# FPGA_MGT.net
KiCad netlist of a schematic drawn in Altium Designer
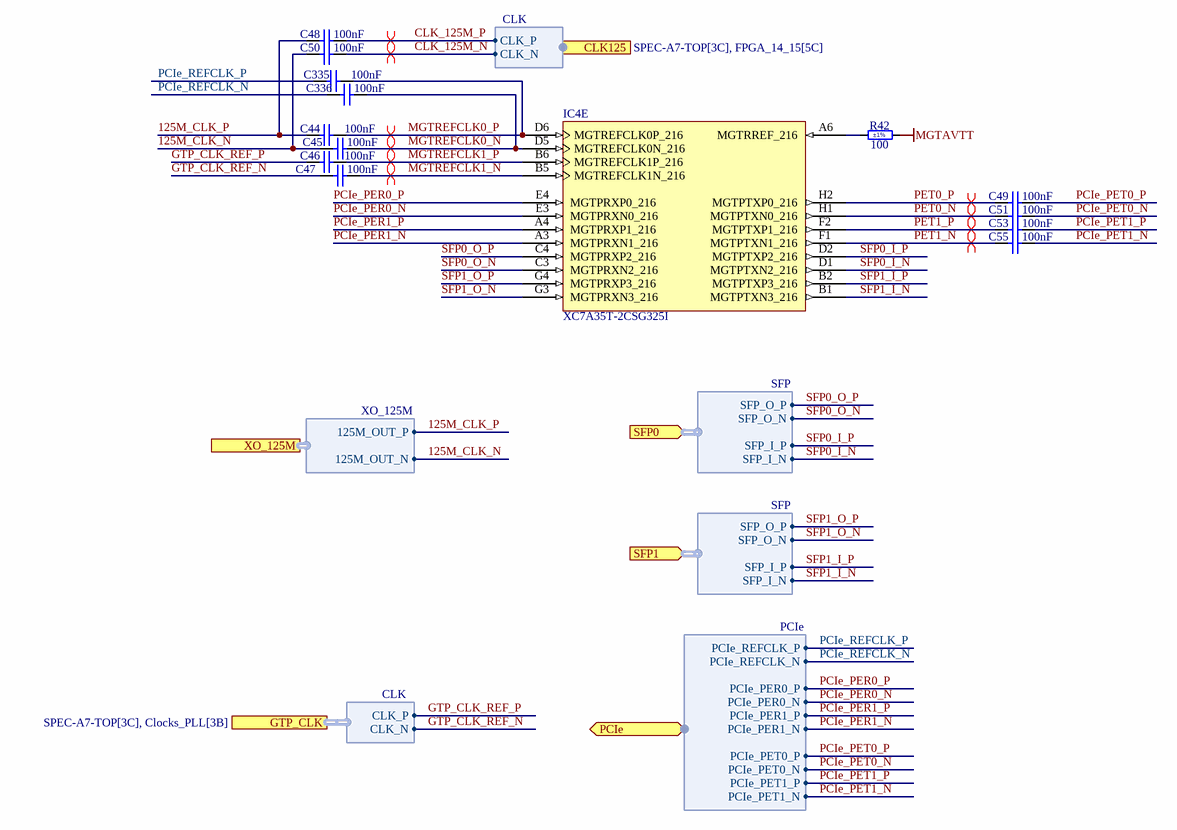
[diagram p0: FPGA_MGT.SchDoc]

(export (version "E")
  (design (tool "Eeschema 10.0.6"))
  (components
    (comp (ref "C44")
      (value "100nF")
      (footprint "CAPC0603X33N")
      (description "Non-polarised capacitor")
      (fields
        (field (name "PART NUMBER") "CC0201_100NF_6.3V_10%_X5R")
        (field (name "VOLTAGE") "6.3V")
        (field (name "AUTHOR") "CERN DEM JLC")
      )
      (libsource (lib "Capacitors") (part "Capacitor - non polarized"))
    )
    (comp (ref "C45")
      (value "100nF")
      (footprint "CAPC0603X33N")
      (description "Non-polarised capacitor")
      (fields
        (field (name "PART NUMBER") "CC0201_100NF_6.3V_10%_X5R")
        (field (name "VOLTAGE") "6.3V")
        (field (name "AUTHOR") "CERN DEM JLC")
      )
      (libsource (lib "Capacitors") (part "Capacitor - non polarized"))
    )
    (comp (ref "C46")
      (value "100nF")
      (footprint "CAPC0603X33N")
      (description "Non-polarised capacitor")
      (fields
        (field (name "PART NUMBER") "CC0201_100NF_6.3V_10%_X5R")
        (field (name "VOLTAGE") "6.3V")
        (field (name "AUTHOR") "CERN DEM JLC")
      )
      (libsource (lib "Capacitors") (part "Capacitor - non polarized"))
    )
    (comp (ref "C47")
      (value "100nF")
      (footprint "CAPC0603X33N")
      (description "Non-polarised capacitor")
      (fields
        (field (name "PART NUMBER") "CC0201_100NF_6.3V_10%_X5R")
        (field (name "VOLTAGE") "6.3V")
        (field (name "AUTHOR") "CERN DEM JLC")
      )
      (libsource (lib "Capacitors") (part "Capacitor - non polarized"))
    )
    (comp (ref "C48")
      (value "100nF")
      (footprint "CAPC0603X33N")
      (description "Non-polarised capacitor")
      (fields
        (field (name "PART NUMBER") "CC0201_100NF_6.3V_10%_X5R")
        (field (name "VOLTAGE") "6.3V")
        (field (name "AUTHOR") "CERN DEM JLC")
      )
      (libsource (lib "Capacitors") (part "Capacitor - non polarized"))
    )
    (comp (ref "C49")
      (value "100nF")
      (footprint "CAPC0603X33N")
      (description "Non-polarised capacitor")
      (fields
        (field (name "PART NUMBER") "CC0201_100NF_6.3V_10%_X5R")
        (field (name "VOLTAGE") "6.3V")
        (field (name "AUTHOR") "CERN DEM JLC")
      )
      (libsource (lib "Capacitors") (part "Capacitor - non polarized"))
    )
    (comp (ref "C50")
      (value "100nF")
      (footprint "CAPC0603X33N")
      (description "Non-polarised capacitor")
      (fields
        (field (name "PART NUMBER") "CC0201_100NF_6.3V_10%_X5R")
        (field (name "VOLTAGE") "6.3V")
        (field (name "AUTHOR") "CERN DEM JLC")
      )
      (libsource (lib "Capacitors") (part "Capacitor - non polarized"))
    )
    (comp (ref "C51")
      (value "100nF")
      (footprint "CAPC0603X33N")
      (description "Non-polarised capacitor")
      (fields
        (field (name "PART NUMBER") "CC0201_100NF_6.3V_10%_X5R")
        (field (name "VOLTAGE") "6.3V")
        (field (name "AUTHOR") "CERN DEM JLC")
      )
      (libsource (lib "Capacitors") (part "Capacitor - non polarized"))
    )
    (comp (ref "C53")
      (value "100nF")
      (footprint "CAPC0603X33N")
      (description "Non-polarised capacitor")
      (fields
        (field (name "PART NUMBER") "CC0201_100NF_6.3V_10%_X5R")
        (field (name "VOLTAGE") "6.3V")
        (field (name "AUTHOR") "CERN DEM JLC")
      )
      (libsource (lib "Capacitors") (part "Capacitor - non polarized"))
    )
    (comp (ref "C55")
      (value "100nF")
      (footprint "CAPC0603X33N")
      (description "Non-polarised capacitor")
      (fields
        (field (name "PART NUMBER") "CC0201_100NF_6.3V_10%_X5R")
        (field (name "VOLTAGE") "6.3V")
        (field (name "AUTHOR") "CERN DEM JLC")
      )
      (libsource (lib "Capacitors") (part "Capacitor - non polarized"))
    )
    (comp (ref "C335")
      (value "100nF")
      (footprint "CAPC0603X33N")
      (description "Non-polarised capacitor")
      (fields
        (field (name "PART NUMBER") "CC0201_100NF_6.3V_10%_X5R")
        (field (name "VOLTAGE") "6.3V")
        (field (name "AUTHOR") "CERN DEM JLC")
      )
      (libsource (lib "Capacitors") (part "Capacitor - non polarized"))
    )
    (comp (ref "C336")
      (value "100nF")
      (footprint "CAPC0603X33N")
      (description "Non-polarised capacitor")
      (fields
        (field (name "PART NUMBER") "CC0201_100NF_6.3V_10%_X5R")
        (field (name "VOLTAGE") "6.3V")
        (field (name "AUTHOR") "CERN DEM JLC")
      )
      (libsource (lib "Capacitors") (part "Capacitor - non polarized"))
    )
    (comp (ref "IC4")
      (value "XC7A35T-2CSG325I")
      (footprint "CSG325")
      (description "Artix-7 FPGA, 150 User I/Os, 4 GTP, 324-Ball BGA, Speed Grade 2, Industrial Grade, Pb-Free")
      (fields (field (name "MANUFACTURER") "Xilinx"))
      (libsource (lib "Altium Content Vault") (part "XLNX-XC7A35T-CSG325"))
    )
    (comp (ref "R42")
      (value "100")
      (footprint "RESC1005X40N")
      (description "Resistor - 1%")
      (fields
        (field (name "TOLERANCE") "±1%")
        (field (name "PART NUMBER") "R0402_100R_1%_0.0625W_100PPM")
        (field (name "POWER") "0.0625W")
        (field (name "AUTHOR") "CERN DEM JLC")
      )
      (libsource (lib "Resistors") (part "Resistor - 1%"))
    )
  )
  (nets
    (net (code "5") (name "/125M_CLK_N") (class "Default")
      (node (ref "C45") (pin "1") (pinfunction "1_1") (pintype "passive"))
      (node (ref "C50") (pin "1") (pinfunction "1_1") (pintype "passive"))
    )
    (net (code "6") (name "/125M_CLK_P") (class "Default")
      (node (ref "C44") (pin "1") (pinfunction "1_1") (pintype "passive"))
      (node (ref "C48") (pin "1") (pinfunction "1_1") (pintype "passive"))
    )
    (net (code "7") (name "/CLK_125M_N") (class "Default")
      (node (ref "C50") (pin "2") (pinfunction "2_2") (pintype "passive"))
    )
    (net (code "8") (name "/CLK_125M_P") (class "Default")
      (node (ref "C48") (pin "2") (pinfunction "2_2") (pintype "passive"))
    )
    (net (code "9") (name "/GTP_CLK_REF_N") (class "Default")
      (node (ref "C47") (pin "1") (pinfunction "1_1") (pintype "passive"))
    )
    (net (code "10") (name "/GTP_CLK_REF_P") (class "Default")
      (node (ref "C46") (pin "1") (pinfunction "1_1") (pintype "passive"))
    )
    (net (code "11") (name "/MGTREFCLK0_N") (class "Default")
      (node (ref "C336") (pin "2") (pinfunction "2_2") (pintype "passive"))
      (node (ref "C45") (pin "2") (pinfunction "2_2") (pintype "passive"))
      (node (ref "IC4") (pin "D5") (pinfunction "MGTREFCLK0N_216_D5") (pintype "input"))
    )
    (net (code "12") (name "/MGTREFCLK0_P") (class "Default")
      (node (ref "C335") (pin "2") (pinfunction "2_2") (pintype "passive"))
      (node (ref "C44") (pin "2") (pinfunction "2_2") (pintype "passive"))
      (node (ref "IC4") (pin "D6") (pinfunction "MGTREFCLK0P_216_D6") (pintype "input"))
    )
    (net (code "13") (name "/MGTREFCLK1_N") (class "Default")
      (node (ref "C47") (pin "2") (pinfunction "2_2") (pintype "passive"))
      (node (ref "IC4") (pin "B5") (pinfunction "MGTREFCLK1N_216_B5") (pintype "input"))
    )
    (net (code "14") (name "/MGTREFCLK1_P") (class "Default")
      (node (ref "C46") (pin "2") (pinfunction "2_2") (pintype "passive"))
      (node (ref "IC4") (pin "B6") (pinfunction "MGTREFCLK1P_216_B6") (pintype "input"))
    )
    (net (code "15") (name "/PCIe_PER0_N") (class "Default")
      (node (ref "IC4") (pin "E3") (pinfunction "MGTPRXN0_216_E3") (pintype "input"))
    )
    (net (code "16") (name "/PCIe_PER0_P") (class "Default")
      (node (ref "IC4") (pin "E4") (pinfunction "MGTPRXP0_216_E4") (pintype "input"))
    )
    (net (code "17") (name "/PCIe_PER1_N") (class "Default")
      (node (ref "IC4") (pin "A3") (pinfunction "MGTPRXN1_216_A3") (pintype "input"))
    )
    (net (code "18") (name "/PCIe_PER1_P") (class "Default")
      (node (ref "IC4") (pin "A4") (pinfunction "MGTPRXP1_216_A4") (pintype "input"))
    )
    (net (code "19") (name "/PCIe_PET0_N") (class "Default")
      (node (ref "C51") (pin "2") (pinfunction "2_2") (pintype "passive"))
    )
    (net (code "20") (name "/PCIe_PET0_P") (class "Default")
      (node (ref "C49") (pin "2") (pinfunction "2_2") (pintype "passive"))
    )
    (net (code "21") (name "/PCIe_PET1_N") (class "Default")
      (node (ref "C55") (pin "2") (pinfunction "2_2") (pintype "passive"))
    )
    (net (code "22") (name "/PCIe_PET1_P") (class "Default")
      (node (ref "C53") (pin "2") (pinfunction "2_2") (pintype "passive"))
    )
    (net (code "23") (name "/PCIe_REFCLK_N") (class "Default")
      (node (ref "C336") (pin "1") (pinfunction "1_1") (pintype "passive"))
    )
    (net (code "24") (name "/PCIe_REFCLK_P") (class "Default")
      (node (ref "C335") (pin "1") (pinfunction "1_1") (pintype "passive"))
    )
    (net (code "25") (name "/PET0_N") (class "Default")
      (node (ref "C51") (pin "1") (pinfunction "1_1") (pintype "passive"))
      (node (ref "IC4") (pin "H1") (pinfunction "MGTPTXN0_216_H1") (pintype "output"))
    )
    (net (code "26") (name "/PET0_P") (class "Default")
      (node (ref "C49") (pin "1") (pinfunction "1_1") (pintype "passive"))
      (node (ref "IC4") (pin "H2") (pinfunction "MGTPTXP0_216_H2") (pintype "output"))
    )
    (net (code "27") (name "/PET1_N") (class "Default")
      (node (ref "C55") (pin "1") (pinfunction "1_1") (pintype "passive"))
      (node (ref "IC4") (pin "F1") (pinfunction "MGTPTXN1_216_F1") (pintype "output"))
    )
    (net (code "28") (name "/PET1_P") (class "Default")
      (node (ref "C53") (pin "1") (pinfunction "1_1") (pintype "passive"))
      (node (ref "IC4") (pin "F2") (pinfunction "MGTPTXP1_216_F2") (pintype "output"))
    )
    (net (code "29") (name "/SFP0_I_N") (class "Default")
      (node (ref "IC4") (pin "D1") (pinfunction "MGTPTXN2_216_D1") (pintype "output"))
    )
    (net (code "30") (name "/SFP0_I_P") (class "Default")
      (node (ref "IC4") (pin "D2") (pinfunction "MGTPTXP2_216_D2") (pintype "output"))
    )
    (net (code "31") (name "/SFP0_O_N") (class "Default")
      (node (ref "IC4") (pin "C3") (pinfunction "MGTPRXN2_216_C3") (pintype "input"))
    )
    (net (code "32") (name "/SFP0_O_P") (class "Default")
      (node (ref "IC4") (pin "C4") (pinfunction "MGTPRXP2_216_C4") (pintype "input"))
    )
    (net (code "33") (name "/SFP1_I_N") (class "Default")
      (node (ref "IC4") (pin "B1") (pinfunction "MGTPTXN3_216_B1") (pintype "output"))
    )
    (net (code "34") (name "/SFP1_I_P") (class "Default")
      (node (ref "IC4") (pin "B2") (pinfunction "MGTPTXP3_216_B2") (pintype "output"))
    )
    (net (code "35") (name "/SFP1_O_N") (class "Default")
      (node (ref "IC4") (pin "G3") (pinfunction "MGTPRXN3_216_G3") (pintype "input"))
    )
    (net (code "36") (name "/SFP1_O_P") (class "Default")
      (node (ref "IC4") (pin "G4") (pinfunction "MGTPRXP3_216_G4") (pintype "input"))
    )
    (net (code "41") (name "MGTAVTT") (class "Default")
      (node (ref "R42") (pin "2") (pinfunction "2_2") (pintype "passive"))
    )
    (net (code "42") (name "Net-(IC4E-MGTRREF_216)") (class "Default")
      (node (ref "IC4") (pin "A6") (pinfunction "MGTRREF_216_A6") (pintype "input"))
      (node (ref "R42") (pin "1") (pinfunction "1_1") (pintype "passive"))
    )
  )
)
